# BOC_LED_DIPSWITCH.net
KiCad netlist of a schematic drawn in Altium Designer
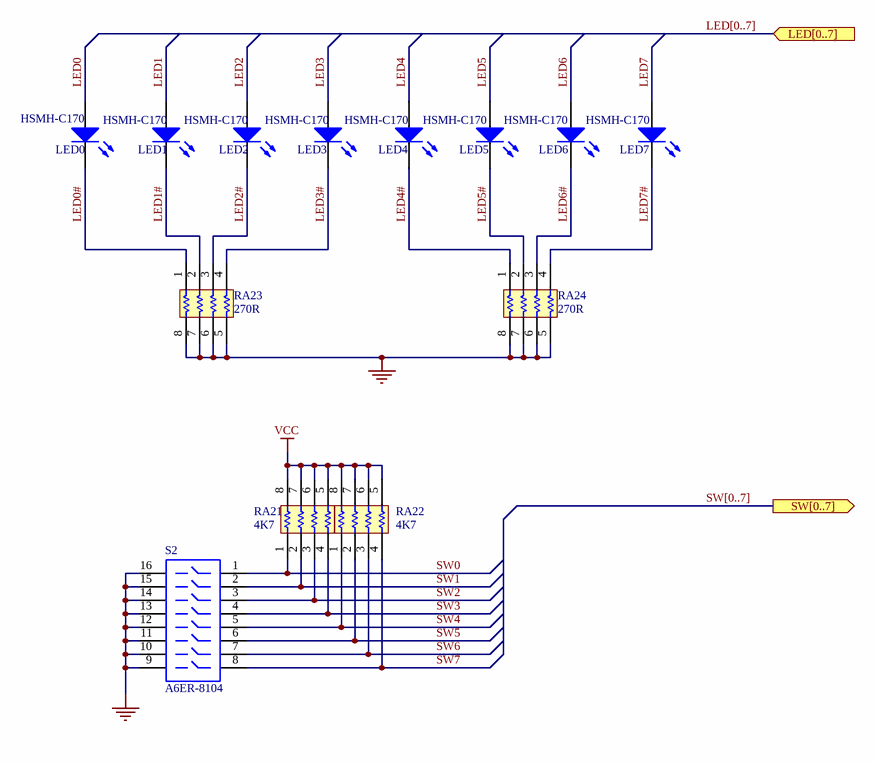
[diagram p0: BOC_LED_DIPSWITCH.SchDoc]

(export (version "E")
  (design (tool "Eeschema 10.0.6"))
  (components
    (comp (ref "LED0")
      (value "HSMH-C170")
      (footprint "Altium Nanoboard Project:SMD _LED")
      (description "Typical RED GaAs SMD LED Agilent make")
      (fields (field (name "MANUFACTURER") "Generic Components") (field (name "PUBLISHER") "Altium Limited"))
      (libsource (lib "Altium Nanoboard Project") (part "HSMX-C670"))
    )
    (comp (ref "LED1")
      (value "HSMH-C170")
      (footprint "Altium Nanoboard Project:SMD _LED")
      (description "Typical RED GaAs SMD LED Agilent make")
      (fields (field (name "MANUFACTURER") "Generic Components") (field (name "PUBLISHER") "Altium Limited"))
      (libsource (lib "Altium Nanoboard Project") (part "HSMX-C670"))
    )
    (comp (ref "LED2")
      (value "HSMH-C170")
      (footprint "Altium Nanoboard Project:SMD _LED")
      (description "Typical RED GaAs SMD LED Agilent make")
      (fields (field (name "MANUFACTURER") "Generic Components") (field (name "PUBLISHER") "Altium Limited"))
      (libsource (lib "Altium Nanoboard Project") (part "HSMX-C670"))
    )
    (comp (ref "LED3")
      (value "HSMH-C170")
      (footprint "Altium Nanoboard Project:SMD _LED")
      (description "Typical RED GaAs SMD LED Agilent make")
      (fields (field (name "MANUFACTURER") "Generic Components") (field (name "PUBLISHER") "Altium Limited"))
      (libsource (lib "Altium Nanoboard Project") (part "HSMX-C670"))
    )
    (comp (ref "LED4")
      (value "HSMH-C170")
      (footprint "Altium Nanoboard Project:SMD _LED")
      (description "Typical RED GaAs SMD LED Agilent make")
      (fields (field (name "MANUFACTURER") "Generic Components") (field (name "PUBLISHER") "Altium Limited"))
      (libsource (lib "Altium Nanoboard Project") (part "HSMX-C670"))
    )
    (comp (ref "LED5")
      (value "HSMH-C170")
      (footprint "Altium Nanoboard Project:SMD _LED")
      (description "Typical RED GaAs SMD LED Agilent make")
      (fields (field (name "MANUFACTURER") "Generic Components") (field (name "PUBLISHER") "Altium Limited"))
      (libsource (lib "Altium Nanoboard Project") (part "HSMX-C670"))
    )
    (comp (ref "LED6")
      (value "HSMH-C170")
      (footprint "Altium Nanoboard Project:SMD _LED")
      (description "Typical RED GaAs SMD LED Agilent make")
      (fields (field (name "MANUFACTURER") "Generic Components") (field (name "PUBLISHER") "Altium Limited"))
      (libsource (lib "Altium Nanoboard Project") (part "HSMX-C670"))
    )
    (comp (ref "LED7")
      (value "HSMH-C170")
      (footprint "Altium Nanoboard Project:SMD _LED")
      (description "Typical RED GaAs SMD LED Agilent make")
      (fields (field (name "MANUFACTURER") "Generic Components") (field (name "PUBLISHER") "Altium Limited"))
      (libsource (lib "Altium Nanoboard Project") (part "HSMX-C670"))
    )
    (comp (ref "RA21")
      (value "4K7")
      (footprint "Altium Nanoboard Project:MNR34")
      (description "3216x4 Resistor Array")
      (libsource (lib "") (part "MNR34_1"))
    )
    (comp (ref "RA22")
      (value "4K7")
      (footprint "Altium Nanoboard Project:MNR34")
      (description "3216x4 Resistor Array")
      (libsource (lib "") (part "MNR34_1"))
    )
    (comp (ref "RA23")
      (value "270R")
      (footprint "Altium Nanoboard Project:MNR34")
      (description "3216x4 Resistor Array")
      (libsource (lib "Altium Nanoboard Project") (part "MNR34"))
    )
    (comp (ref "RA24")
      (value "270R")
      (footprint "Altium Nanoboard Project:MNR34")
      (description "3216x4 Resistor Array")
      (libsource (lib "Altium Nanoboard Project") (part "MNR34"))
    )
    (comp (ref "S2")
      (value "A6ER-8104")
      (footprint "Altium Nanoboard Project:DIP-16-KEY")
      (description "DIP Switch Side actuator long liver Piano Key")
      (fields (field (name "MANUFACTURER") "Generic Components") (field (name "PUBLISHER") "Altium Limited"))
      (libsource (lib "Altium Nanoboard Project") (part "A6ER-8104"))
    )
  )
  (nets
    (net (code "1") (name "/LED0") (class "Default")
      (node (ref "LED0") (pin "1") (pinfunction "A_1") (pintype "passive"))
    )
    (net (code "2") (name "/LED0#") (class "Default")
      (node (ref "LED0") (pin "2") (pinfunction "K_2") (pintype "passive"))
      (node (ref "RA23") (pin "1") (pintype "passive"))
    )
    (net (code "3") (name "/LED1") (class "Default")
      (node (ref "LED1") (pin "1") (pinfunction "A_1") (pintype "passive"))
    )
    (net (code "4") (name "/LED1#") (class "Default")
      (node (ref "LED1") (pin "2") (pinfunction "K_2") (pintype "passive"))
      (node (ref "RA23") (pin "2") (pintype "passive"))
    )
    (net (code "5") (name "/LED2") (class "Default")
      (node (ref "LED2") (pin "1") (pinfunction "A_1") (pintype "passive"))
    )
    (net (code "6") (name "/LED2#") (class "Default")
      (node (ref "LED2") (pin "2") (pinfunction "K_2") (pintype "passive"))
      (node (ref "RA23") (pin "3") (pintype "passive"))
    )
    (net (code "7") (name "/LED3") (class "Default")
      (node (ref "LED3") (pin "1") (pinfunction "A_1") (pintype "passive"))
    )
    (net (code "8") (name "/LED3#") (class "Default")
      (node (ref "LED3") (pin "2") (pinfunction "K_2") (pintype "passive"))
      (node (ref "RA23") (pin "4") (pintype "passive"))
    )
    (net (code "9") (name "/LED4") (class "Default")
      (node (ref "LED4") (pin "1") (pinfunction "A_1") (pintype "passive"))
    )
    (net (code "10") (name "/LED4#") (class "Default")
      (node (ref "LED4") (pin "2") (pinfunction "K_2") (pintype "passive"))
      (node (ref "RA24") (pin "1") (pintype "passive"))
    )
    (net (code "11") (name "/LED5") (class "Default")
      (node (ref "LED5") (pin "1") (pinfunction "A_1") (pintype "passive"))
    )
    (net (code "12") (name "/LED5#") (class "Default")
      (node (ref "LED5") (pin "2") (pinfunction "K_2") (pintype "passive"))
      (node (ref "RA24") (pin "2") (pintype "passive"))
    )
    (net (code "13") (name "/LED6") (class "Default")
      (node (ref "LED6") (pin "1") (pinfunction "A_1") (pintype "passive"))
    )
    (net (code "14") (name "/LED6#") (class "Default")
      (node (ref "LED6") (pin "2") (pinfunction "K_2") (pintype "passive"))
      (node (ref "RA24") (pin "3") (pintype "passive"))
    )
    (net (code "15") (name "/LED7") (class "Default")
      (node (ref "LED7") (pin "1") (pinfunction "A_1") (pintype "passive"))
    )
    (net (code "16") (name "/LED7#") (class "Default")
      (node (ref "LED7") (pin "2") (pinfunction "K_2") (pintype "passive"))
      (node (ref "RA24") (pin "4") (pintype "passive"))
    )
    (net (code "18") (name "/SW0") (class "Default")
      (node (ref "RA21") (pin "1") (pintype "passive"))
      (node (ref "S2") (pin "1") (pinfunction "1_1") (pintype "passive"))
    )
    (net (code "19") (name "/SW1") (class "Default")
      (node (ref "RA21") (pin "2") (pintype "passive"))
      (node (ref "S2") (pin "2") (pinfunction "2_2") (pintype "passive"))
    )
    (net (code "20") (name "/SW2") (class "Default")
      (node (ref "RA21") (pin "3") (pintype "passive"))
      (node (ref "S2") (pin "3") (pinfunction "3_3") (pintype "passive"))
    )
    (net (code "21") (name "/SW3") (class "Default")
      (node (ref "RA21") (pin "4") (pintype "passive"))
      (node (ref "S2") (pin "4") (pinfunction "4_4") (pintype "passive"))
    )
    (net (code "22") (name "/SW4") (class "Default")
      (node (ref "RA22") (pin "1") (pintype "passive"))
      (node (ref "S2") (pin "5") (pinfunction "5_5") (pintype "passive"))
    )
    (net (code "23") (name "/SW5") (class "Default")
      (node (ref "RA22") (pin "2") (pintype "passive"))
      (node (ref "S2") (pin "6") (pinfunction "6_6") (pintype "passive"))
    )
    (net (code "24") (name "/SW6") (class "Default")
      (node (ref "RA22") (pin "3") (pintype "passive"))
      (node (ref "S2") (pin "7") (pinfunction "7_7") (pintype "passive"))
    )
    (net (code "25") (name "/SW7") (class "Default")
      (node (ref "RA22") (pin "4") (pintype "passive"))
      (node (ref "S2") (pin "8") (pinfunction "8_8") (pintype "passive"))
    )
    (net (code "27") (name "GND") (class "Default")
      (node (ref "RA23") (pin "5") (pintype "passive"))
      (node (ref "RA23") (pin "6") (pintype "passive"))
      (node (ref "RA23") (pin "7") (pintype "passive"))
      (node (ref "RA23") (pin "8") (pintype "passive"))
      (node (ref "RA24") (pin "5") (pintype "passive"))
      (node (ref "RA24") (pin "6") (pintype "passive"))
      (node (ref "RA24") (pin "7") (pintype "passive"))
      (node (ref "RA24") (pin "8") (pintype "passive"))
      (node (ref "S2") (pin "10") (pinfunction "10_10") (pintype "passive"))
      (node (ref "S2") (pin "11") (pinfunction "11_11") (pintype "passive"))
      (node (ref "S2") (pin "12") (pinfunction "12_12") (pintype "passive"))
      (node (ref "S2") (pin "13") (pinfunction "13_13") (pintype "passive"))
      (node (ref "S2") (pin "14") (pinfunction "14_14") (pintype "passive"))
      (node (ref "S2") (pin "15") (pinfunction "15_15") (pintype "passive"))
      (node (ref "S2") (pin "16") (pinfunction "16_16") (pintype "passive"))
      (node (ref "S2") (pin "9") (pinfunction "9_9") (pintype "passive"))
    )
    (net (code "28") (name "VCC") (class "Default")
      (node (ref "RA21") (pin "5") (pintype "passive"))
      (node (ref "RA21") (pin "6") (pintype "passive"))
      (node (ref "RA21") (pin "7") (pintype "passive"))
      (node (ref "RA21") (pin "8") (pintype "passive"))
      (node (ref "RA22") (pin "5") (pintype "passive"))
      (node (ref "RA22") (pin "6") (pintype "passive"))
      (node (ref "RA22") (pin "7") (pintype "passive"))
      (node (ref "RA22") (pin "8") (pintype "passive"))
    )
  )
)
